# FT-991A_PAT.net
KiCad netlist of a schematic drawn in EAGLE
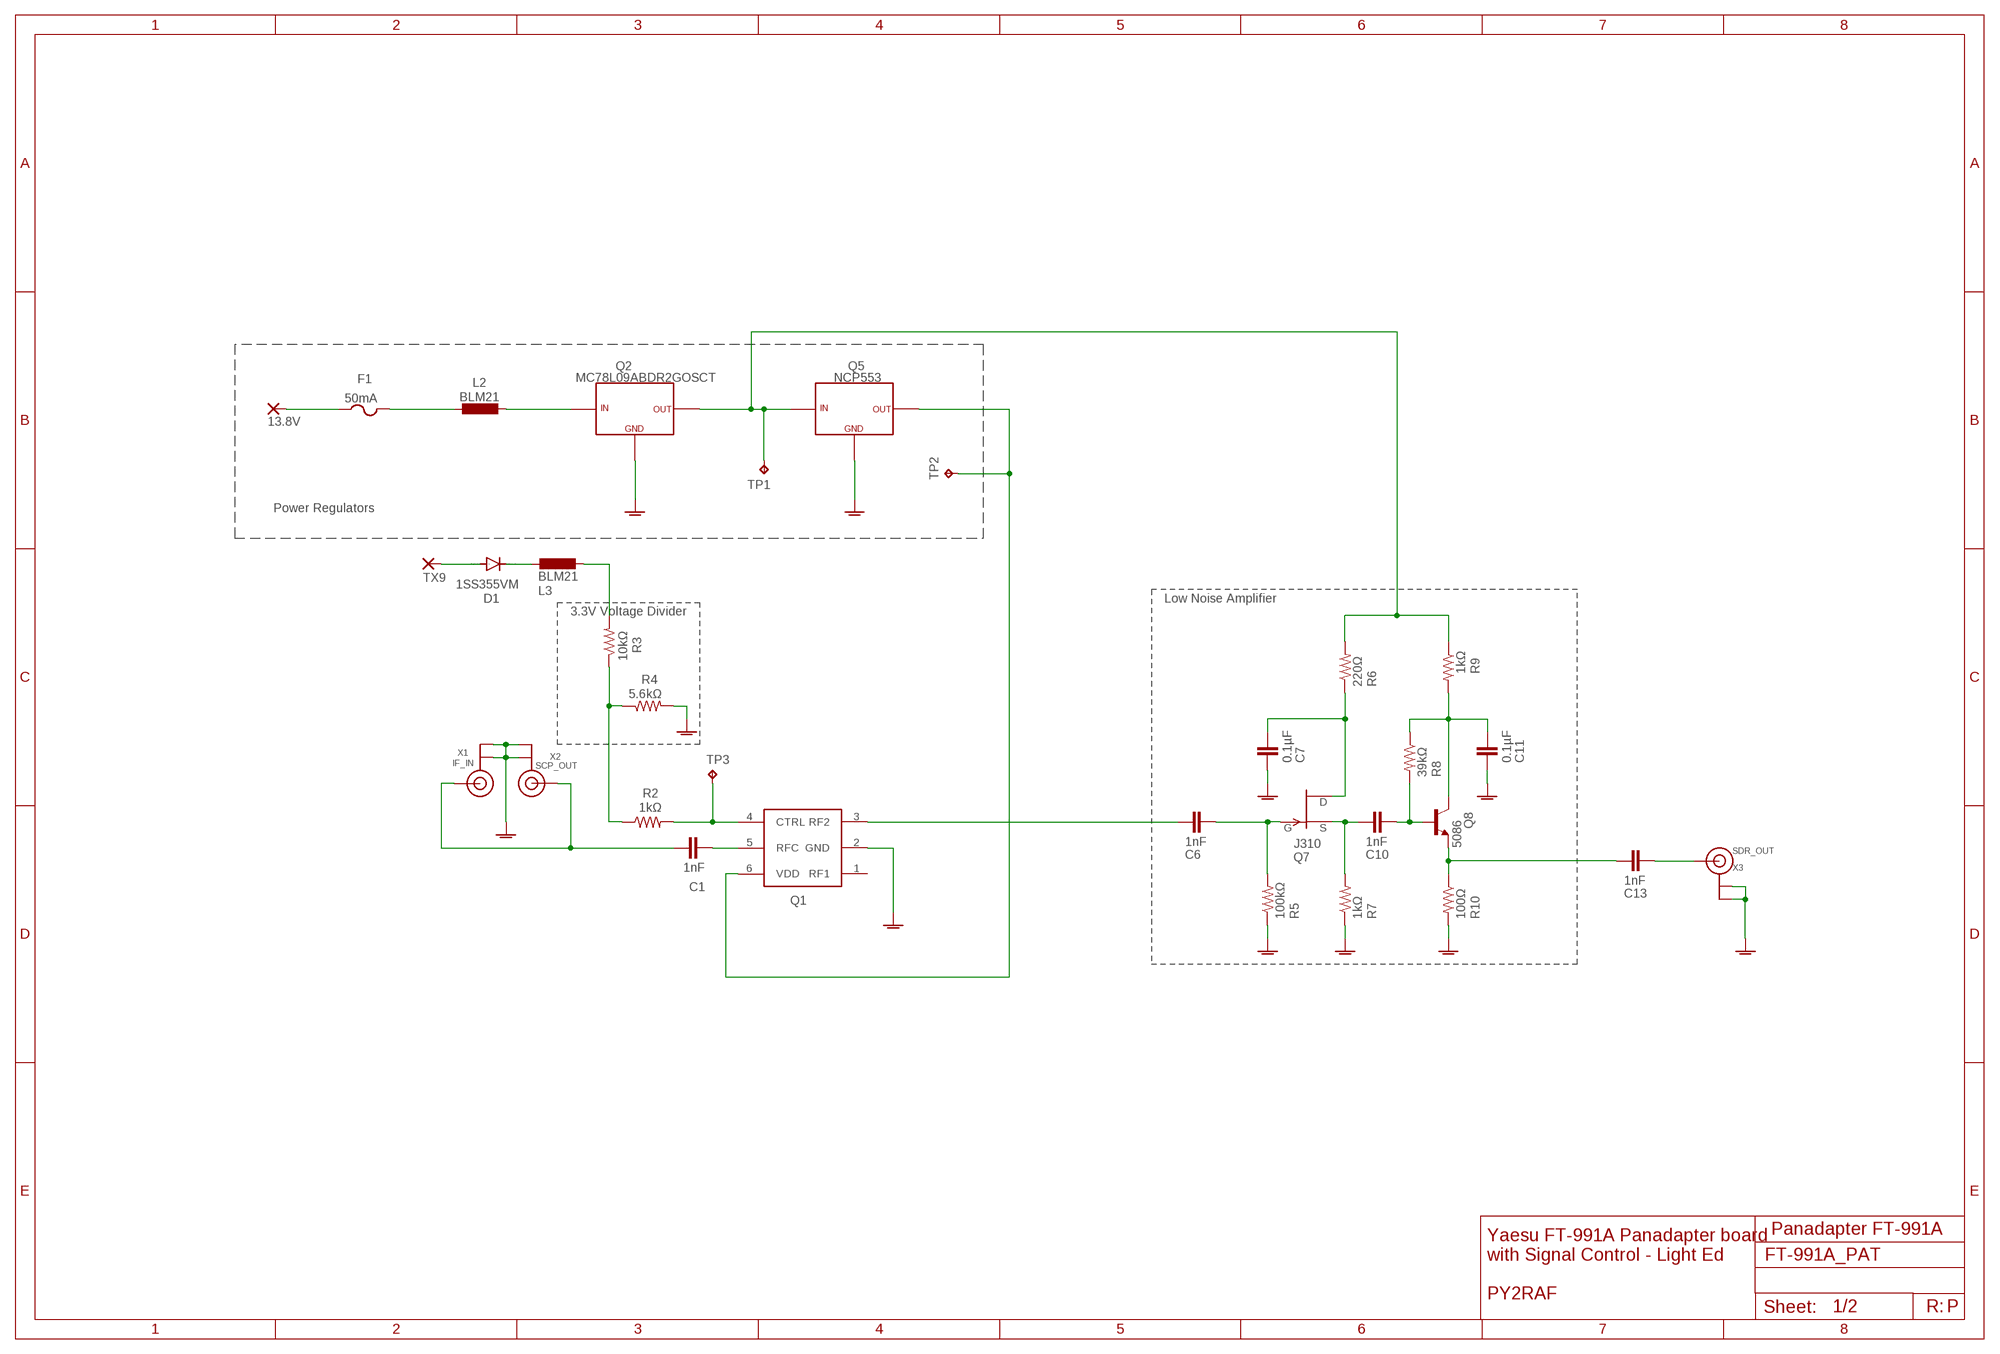
[diagram p0: schematic, sheet 1]
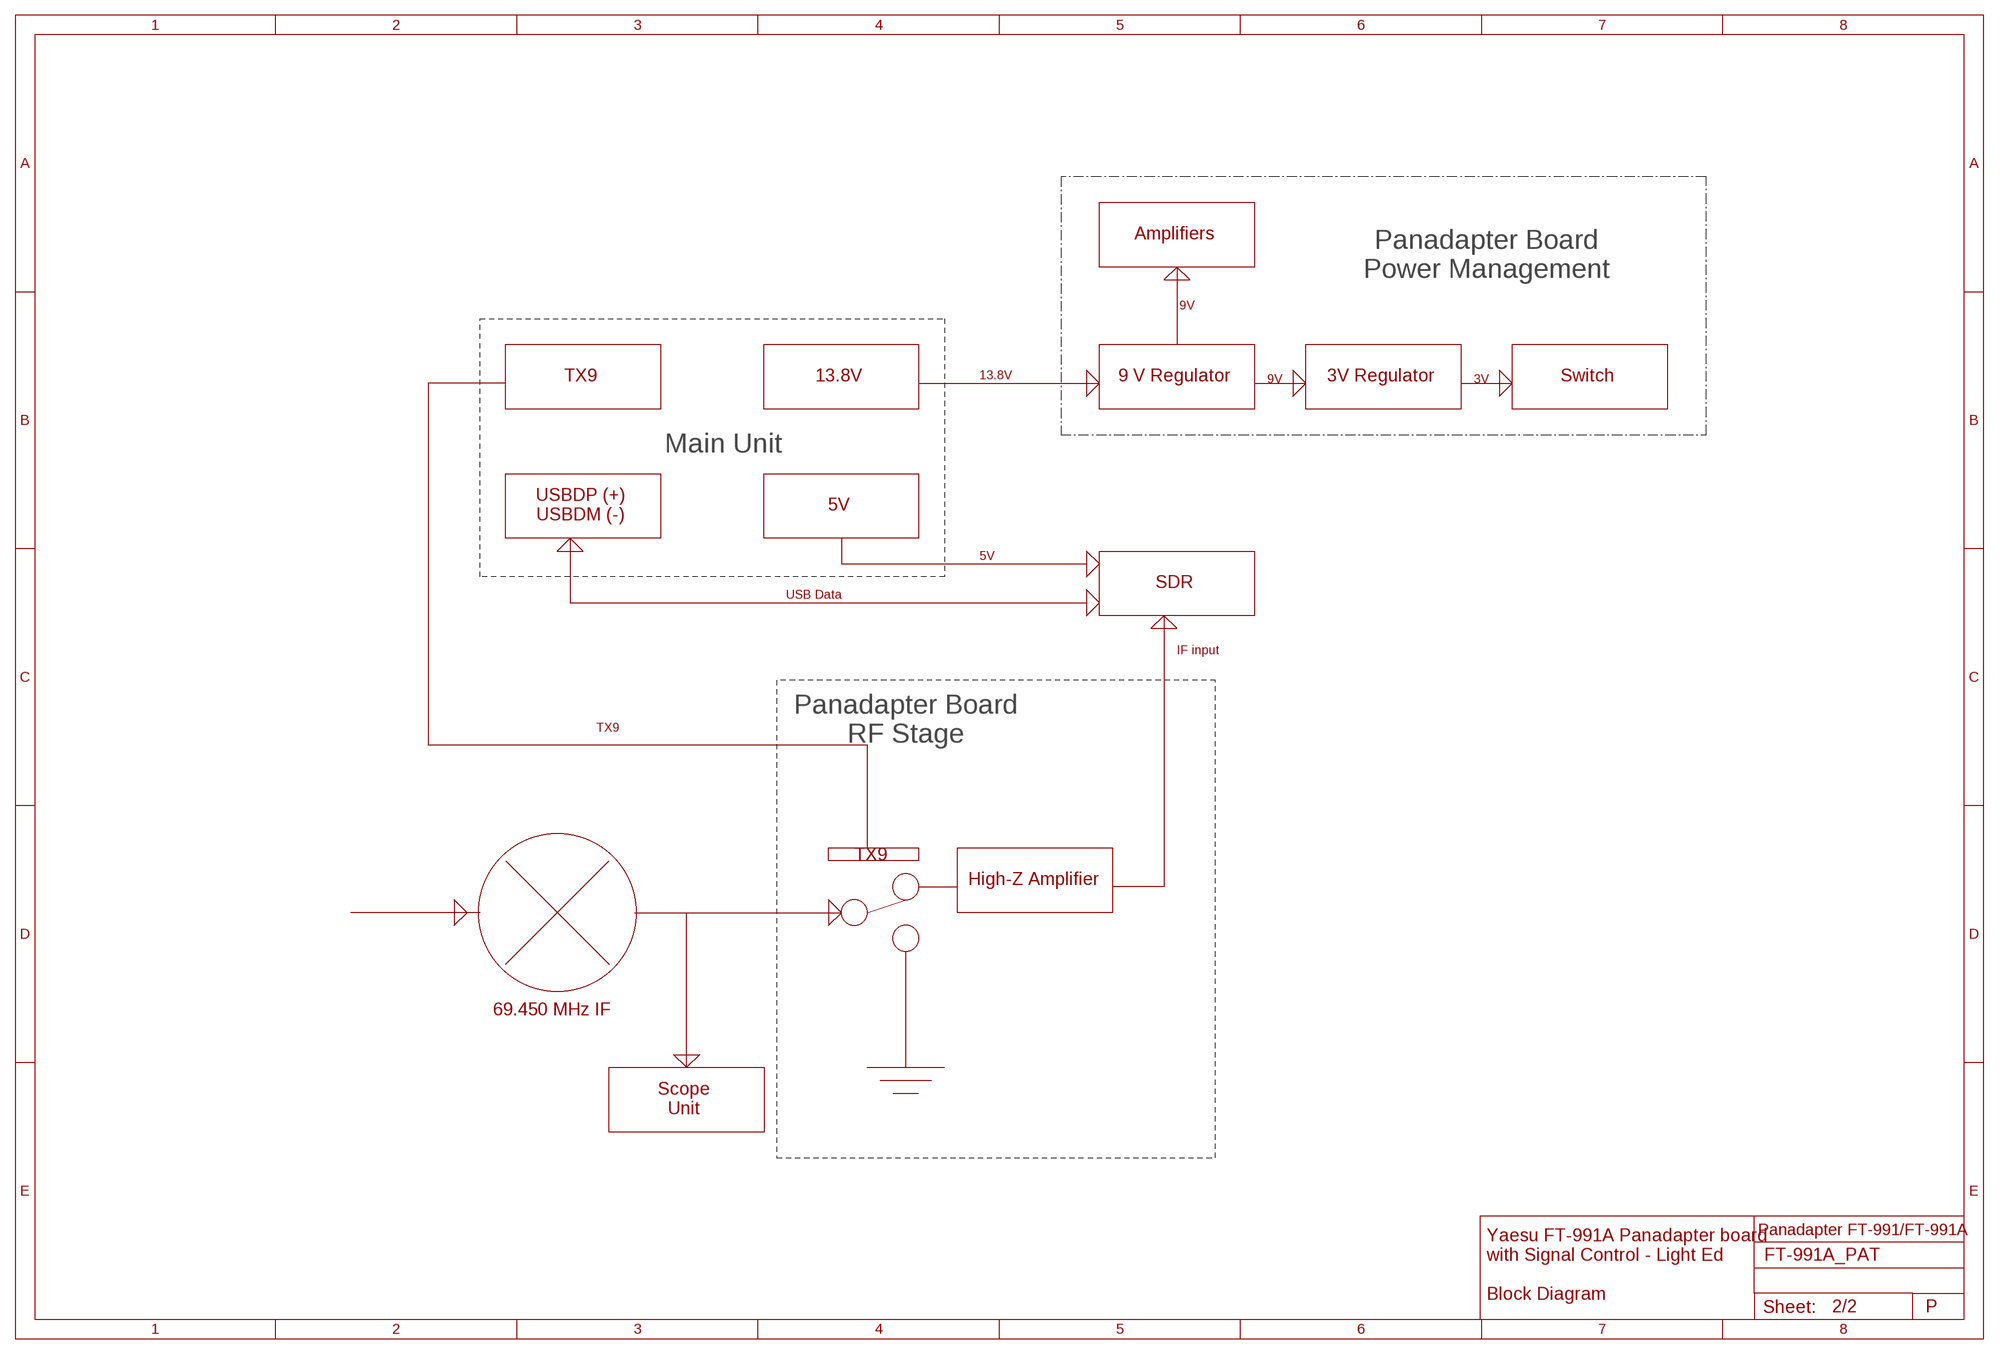
[diagram p1: schematic, sheet 2]

(export (version "E")
  (design (tool "Eeschema 10.0.6"))
  (components
    (comp (ref "13.8V")
      (value "13.8V")
      (footprint "eagle-import:SMD1,27-2,54")
      (libsource (lib "eagle-import") (part "WIREPADSMD1,27-254"))
    )
    (comp (ref "C1")
      (value "1nF")
      (footprint "eagle-import:C3216")
      (libsource (lib "eagle-import") (part "C-EUC3216"))
    )
    (comp (ref "C6")
      (value "1nF")
      (footprint "eagle-import:C3216")
      (libsource (lib "eagle-import") (part "C-EUC3216"))
    )
    (comp (ref "C7")
      (value "0.1µF")
      (footprint "eagle-import:C3216")
      (libsource (lib "eagle-import") (part "C-EUC3216"))
    )
    (comp (ref "C10")
      (value "1nF")
      (footprint "eagle-import:C3216")
      (libsource (lib "eagle-import") (part "C-EUC3216"))
    )
    (comp (ref "C11")
      (value "0.1µF")
      (footprint "eagle-import:C3216")
      (libsource (lib "eagle-import") (part "C-EUC3216"))
    )
    (comp (ref "C13")
      (value "1nF")
      (footprint "eagle-import:C3216")
      (libsource (lib "eagle-import") (part "C-EUC3216"))
    )
    (comp (ref "D1")
      (value "1SS355VM")
      (footprint "eagle-import:SOD323-W")
      (libsource (lib "eagle-import") (part "DIODE-SOD323-W"))
    )
    (comp (ref "F1")
      (value "50mA")
      (footprint "eagle-import:R1206")
      (libsource (lib "eagle-import") (part "PTCFUSE-1206"))
    )
    (comp (ref "L2")
      (value "BLM21")
      (footprint "eagle-import:L0805")
      (libsource (lib "eagle-import") (part "L-EU"))
    )
    (comp (ref "L3")
      (value "BLM21")
      (footprint "eagle-import:L0805")
      (libsource (lib "eagle-import") (part "L-EU"))
    )
    (comp (ref "PAD3")
      (value "TX9")
      (footprint "eagle-import:SMD1,27-2,54")
      (libsource (lib "eagle-import") (part "WIREPADSMD1,27-254"))
    )
    (comp (ref "Q1")
      (value "PE4259")
      (footprint "eagle-import:SC-70")
      (libsource (lib "eagle-import") (part "PE4259"))
    )
    (comp (ref "Q2")
      (value "MC78L09ABDR2GOSCT")
      (footprint "eagle-import:SOIC8")
      (fields (field (name "VOLTAGE") "9V"))
      (libsource (lib "eagle-import") (part "MC78L09ABDR2GOSCT"))
    )
    (comp (ref "Q5")
      (value "NCP553")
      (footprint "eagle-import:SC-82AB")
      (libsource (lib "eagle-import") (part "NCP553"))
    )
    (comp (ref "Q7")
      (value "J310")
      (footprint "eagle-import:SOT23")
      (fields (field (name "SPICEPREFIX") "J"))
      (libsource (lib "eagle-import") (part "?20SST1"))
    )
    (comp (ref "Q8")
      (value "5086")
      (footprint "eagle-import:2-2H1A")
      (libsource (lib "eagle-import") (part "2SC5086"))
    )
    (comp (ref "R2")
      (value "1kΩ")
      (footprint "eagle-import:R3216")
      (libsource (lib "eagle-import") (part "R-US_R3216"))
    )
    (comp (ref "R3")
      (value "10kΩ")
      (footprint "eagle-import:R3216")
      (libsource (lib "eagle-import") (part "R-US_R3216"))
    )
    (comp (ref "R4")
      (value "5.6kΩ")
      (footprint "eagle-import:R3216")
      (libsource (lib "eagle-import") (part "R-US_R3216"))
    )
    (comp (ref "R5")
      (value "100kΩ")
      (footprint "eagle-import:R3216")
      (libsource (lib "eagle-import") (part "R-US_R3216"))
    )
    (comp (ref "R6")
      (value "220Ω")
      (footprint "eagle-import:R3216")
      (libsource (lib "eagle-import") (part "R-US_R3216"))
    )
    (comp (ref "R7")
      (value "1kΩ")
      (footprint "eagle-import:R3216")
      (libsource (lib "eagle-import") (part "R-US_R3216"))
    )
    (comp (ref "R8")
      (value "39kΩ")
      (footprint "eagle-import:R3216")
      (libsource (lib "eagle-import") (part "R-US_R3216"))
    )
    (comp (ref "R9")
      (value "1kΩ")
      (footprint "eagle-import:R3216")
      (libsource (lib "eagle-import") (part "R-US_R3216"))
    )
    (comp (ref "R10")
      (value "100Ω")
      (footprint "eagle-import:R3216")
      (libsource (lib "eagle-import") (part "R-US_R3216"))
    )
    (comp (ref "TP1")
      (value "9V")
      (footprint "eagle-import:B1,27")
      (libsource (lib "eagle-import") (part "TPB1,27"))
    )
    (comp (ref "TP2")
      (value "3V")
      (footprint "eagle-import:B1,27")
      (libsource (lib "eagle-import") (part "TPB1,27"))
    )
    (comp (ref "TP3")
      (value "3V")
      (footprint "eagle-import:B1,27")
      (libsource (lib "eagle-import") (part "TPB1,27"))
    )
    (comp (ref "X1")
      (value "IF_IN")
      (footprint "eagle-import:U.FL")
      (libsource (lib "eagle-import") (part "ANTENNA_U.FL"))
    )
    (comp (ref "X2")
      (value "SCP_OUT")
      (footprint "eagle-import:U.FL")
      (libsource (lib "eagle-import") (part "ANTENNA_U.FL"))
    )
    (comp (ref "X3")
      (value "SDR_OUT")
      (footprint "eagle-import:U.FL")
      (libsource (lib "eagle-import") (part "ANTENNA_U.FL"))
    )
  )
  (nets
    (net (code "1") (name "GNDA") (class "Default")
      (node (ref "C11") (pin "2") (pinfunction "2_2") (pintype "passive"))
      (node (ref "C7") (pin "2") (pinfunction "2_2") (pintype "passive"))
      (node (ref "Q1") (pin "2") (pinfunction "GND_2") (pintype "bidirectional"))
      (node (ref "Q2") (pin "2") (pinfunction "GN_2") (pintype "bidirectional"))
      (node (ref "Q2") (pin "3") (pinfunction "GN_3") (pintype "bidirectional"))
      (node (ref "Q2") (pin "6") (pinfunction "GN_6") (pintype "bidirectional"))
      (node (ref "Q2") (pin "7") (pinfunction "GN_7") (pintype "bidirectional"))
      (node (ref "Q5") (pin "1") (pinfunction "GN_1") (pintype "bidirectional"))
      (node (ref "R10") (pin "2") (pinfunction "2_2") (pintype "passive"))
      (node (ref "R4") (pin "2") (pinfunction "2_2") (pintype "passive"))
      (node (ref "R5") (pin "1") (pinfunction "1_1") (pintype "passive"))
      (node (ref "R7") (pin "1") (pinfunction "1_1") (pintype "passive"))
      (node (ref "X1") (pin "1") (pinfunction "GND_1") (pintype "passive"))
      (node (ref "X1") (pin "2") (pinfunction "GND_2") (pintype "passive"))
      (node (ref "X2") (pin "1") (pinfunction "GND_1") (pintype "passive"))
      (node (ref "X2") (pin "2") (pinfunction "GND_2") (pintype "passive"))
      (node (ref "X3") (pin "1") (pinfunction "GND_1") (pintype "passive"))
      (node (ref "X3") (pin "2") (pinfunction "GND_2") (pintype "passive"))
    )
    (net (code "2") (name "Net-(13.8V-P)") (class "Default")
      (node (ref "13.8V") (pin "1") (pinfunction "P_1") (pintype "passive"))
      (node (ref "F1") (pin "1") (pinfunction "1_1") (pintype "passive"))
    )
    (net (code "3") (name "Net-(D1-PadC)") (class "Default")
      (node (ref "D1") (pin "C") (pinfunction "C_C") (pintype "passive"))
      (node (ref "L3") (pin "1") (pinfunction "1_1") (pintype "passive"))
    )
    (net (code "4") (name "Net-(F1-Pad2)") (class "Default")
      (node (ref "F1") (pin "2") (pinfunction "2_2") (pintype "passive"))
      (node (ref "L2") (pin "2") (pinfunction "2_2") (pintype "passive"))
    )
    (net (code "5") (name "Net-(L3-Pad2)") (class "Default")
      (node (ref "L3") (pin "2") (pinfunction "2_2") (pintype "passive"))
      (node (ref "R3") (pin "2") (pinfunction "2_2") (pintype "passive"))
    )
    (net (code "6") (name "Net-(PAD3-P)") (class "Default")
      (node (ref "D1") (pin "A") (pinfunction "A_A") (pintype "passive"))
      (node (ref "PAD3") (pin "1") (pinfunction "P_1") (pintype "passive"))
    )
    (net (code "7") (name "Net-(Q1-CTRL)") (class "Default")
      (node (ref "Q1") (pin "4") (pinfunction "CTRL_4") (pintype "input"))
      (node (ref "R2") (pin "2") (pinfunction "2_2") (pintype "passive"))
      (node (ref "TP3") (pin "TP") (pinfunction "TP_TP") (pintype "input"))
    )
    (net (code "8") (name "Net-(Q1-RF2)") (class "Default")
      (node (ref "C6") (pin "1") (pinfunction "1_1") (pintype "passive"))
      (node (ref "Q1") (pin "3") (pinfunction "RF2_3") (pintype "bidirectional"))
    )
    (net (code "9") (name "Net-(Q1-RFC)") (class "Default")
      (node (ref "C1") (pin "2") (pinfunction "2_2") (pintype "passive"))
      (node (ref "Q1") (pin "5") (pinfunction "RFC_5") (pintype "bidirectional"))
    )
    (net (code "10") (name "Net-(Q1-VDD)") (class "Default")
      (node (ref "Q1") (pin "6") (pinfunction "VDD_6") (pintype "power_in"))
      (node (ref "Q5") (pin "3") (pinfunction "OUT_3") (pintype "bidirectional"))
      (node (ref "TP2") (pin "TP") (pinfunction "TP_TP") (pintype "input"))
    )
    (net (code "11") (name "Net-(Q2-IN)") (class "Default")
      (node (ref "L2") (pin "1") (pinfunction "1_1") (pintype "passive"))
      (node (ref "Q2") (pin "8") (pinfunction "IN_8") (pintype "bidirectional"))
    )
    (net (code "12") (name "Net-(Q2-OUT)") (class "Default")
      (node (ref "Q2") (pin "1") (pinfunction "OUT_1") (pintype "bidirectional"))
      (node (ref "Q5") (pin "2") (pinfunction "IN_2") (pintype "bidirectional"))
      (node (ref "R6") (pin "2") (pinfunction "2_2") (pintype "passive"))
      (node (ref "R9") (pin "1") (pinfunction "1_1") (pintype "passive"))
      (node (ref "TP1") (pin "TP") (pinfunction "TP_TP") (pintype "input"))
    )
    (net (code "13") (name "Net-(Q7-D)") (class "Default")
      (node (ref "C7") (pin "1") (pinfunction "1_1") (pintype "passive"))
      (node (ref "Q7") (pin "1") (pinfunction "D_1") (pintype "passive"))
      (node (ref "R6") (pin "1") (pinfunction "1_1") (pintype "passive"))
    )
    (net (code "14") (name "Net-(Q7-G)") (class "Default")
      (node (ref "C6") (pin "2") (pinfunction "2_2") (pintype "passive"))
      (node (ref "Q7") (pin "3") (pinfunction "G_3") (pintype "passive"))
      (node (ref "R5") (pin "2") (pinfunction "2_2") (pintype "passive"))
    )
    (net (code "15") (name "Net-(Q7-S)") (class "Default")
      (node (ref "C10") (pin "1") (pinfunction "1_1") (pintype "passive"))
      (node (ref "Q7") (pin "2") (pinfunction "S_2") (pintype "passive"))
      (node (ref "R7") (pin "2") (pinfunction "2_2") (pintype "passive"))
    )
    (net (code "16") (name "Net-(Q8-B)") (class "Default")
      (node (ref "C10") (pin "2") (pinfunction "2_2") (pintype "passive"))
      (node (ref "Q8") (pin "1") (pinfunction "B_1") (pintype "passive"))
      (node (ref "R8") (pin "2") (pinfunction "2_2") (pintype "passive"))
    )
    (net (code "17") (name "Net-(Q8-C)") (class "Default")
      (node (ref "C11") (pin "1") (pinfunction "1_1") (pintype "passive"))
      (node (ref "Q8") (pin "3") (pinfunction "C_3") (pintype "passive"))
      (node (ref "R8") (pin "1") (pinfunction "1_1") (pintype "passive"))
      (node (ref "R9") (pin "2") (pinfunction "2_2") (pintype "passive"))
    )
    (net (code "18") (name "Net-(Q8-E)") (class "Default")
      (node (ref "C13") (pin "1") (pinfunction "1_1") (pintype "passive"))
      (node (ref "Q8") (pin "2") (pinfunction "E_2") (pintype "passive"))
      (node (ref "R10") (pin "1") (pinfunction "1_1") (pintype "passive"))
    )
    (net (code "19") (name "Net-(R2-Pad1)") (class "Default")
      (node (ref "R2") (pin "1") (pinfunction "1_1") (pintype "passive"))
      (node (ref "R3") (pin "1") (pinfunction "1_1") (pintype "passive"))
      (node (ref "R4") (pin "1") (pinfunction "1_1") (pintype "passive"))
    )
    (net (code "20") (name "Net-(X1-SIGNAL)") (class "Default")
      (node (ref "C1") (pin "1") (pinfunction "1_1") (pintype "passive"))
      (node (ref "X1") (pin "3") (pinfunction "SIGNAL_3") (pintype "passive"))
      (node (ref "X2") (pin "3") (pinfunction "SIGNAL_3") (pintype "passive"))
    )
    (net (code "21") (name "Net-(X3-SIGNAL)") (class "Default")
      (node (ref "C13") (pin "2") (pinfunction "2_2") (pintype "passive"))
      (node (ref "X3") (pin "3") (pinfunction "SIGNAL_3") (pintype "passive"))
    )
    (net (code "22") (name "unconnected-(Q1-RF1-Pad1)") (class "Default")
      (node (ref "Q1") (pin "1") (pinfunction "RF1_1") (pintype "bidirectional"))
    )
  )
)
